# hitchBOT-on-a-board.net
KiCad netlist of a schematic drawn in EAGLE
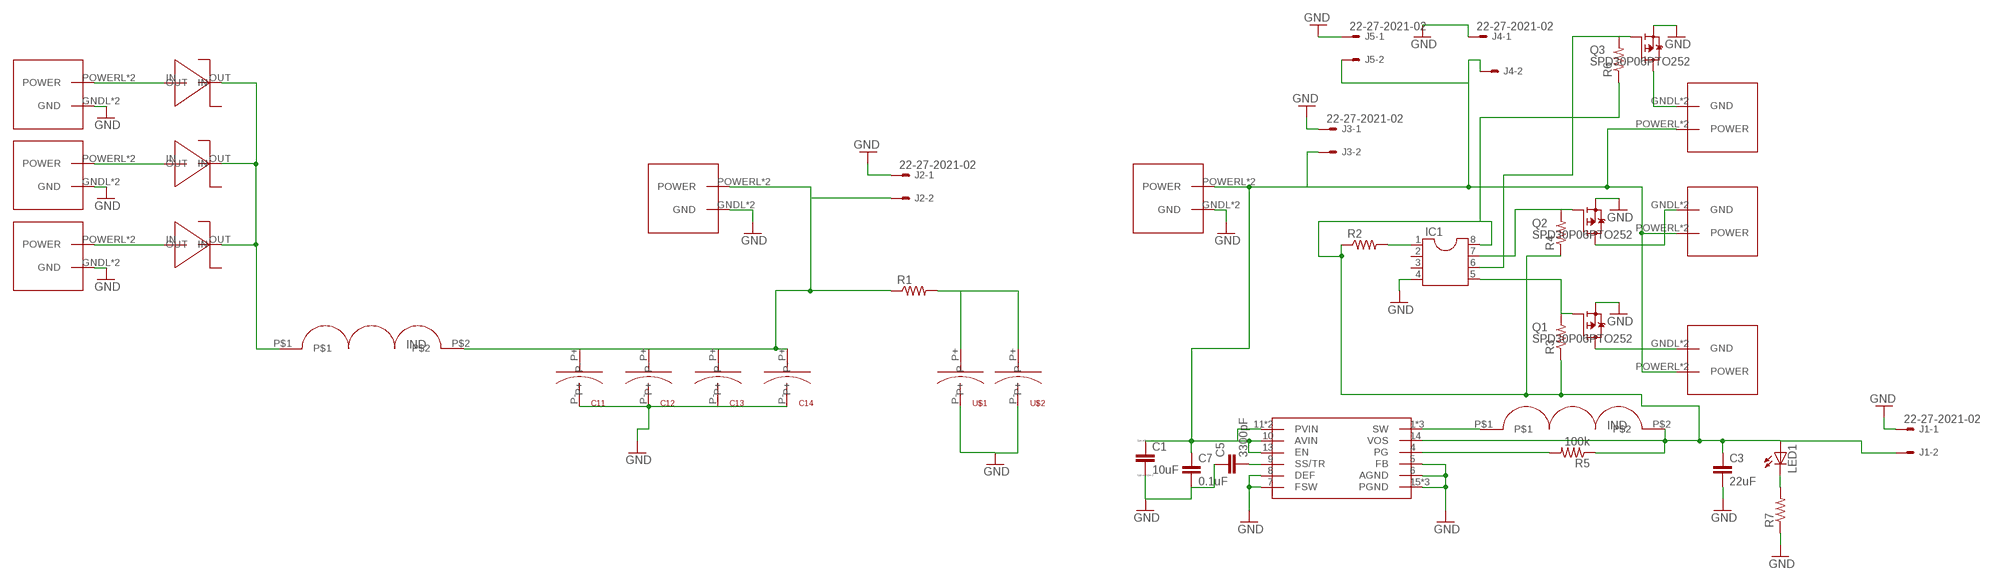
[diagram p0: schematic, sheet 1]

(export (version "E")
  (design (tool "Eeschema 10.0.6"))
  (components
    (comp (ref "C1")
      (value "10uF")
      (footprint "eagle-import:C1210")
      (libsource (lib "eagle-import") (part "CC1210"))
    )
    (comp (ref "C3")
      (value "22uF")
      (footprint "eagle-import:C0805")
      (libsource (lib "eagle-import") (part "C-EUC0805"))
    )
    (comp (ref "C5")
      (value "3300pF")
      (footprint "eagle-import:C0603")
      (libsource (lib "eagle-import") (part "C-EUC0603"))
    )
    (comp (ref "C7")
      (value "0.1uF")
      (footprint "eagle-import:C0603")
      (libsource (lib "eagle-import") (part "C-EUC0603"))
    )
    (comp (ref "C11")
      (value "SMD-CAP-NICHICON-8MM")
      (footprint "eagle-import:SMD-CAP-8MM")
      (libsource (lib "eagle-import") (part "SMD-CAP-NICHICON-8MM"))
    )
    (comp (ref "C12")
      (value "SMD-CAP-NICHICON-8MM")
      (footprint "eagle-import:SMD-CAP-8MM")
      (libsource (lib "eagle-import") (part "SMD-CAP-NICHICON-8MM"))
    )
    (comp (ref "C13")
      (value "SMD-CAP-NICHICON-8MM")
      (footprint "eagle-import:SMD-CAP-8MM")
      (libsource (lib "eagle-import") (part "SMD-CAP-NICHICON-8MM"))
    )
    (comp (ref "C14")
      (value "SMD-CAP-NICHICON-8MM")
      (footprint "eagle-import:SMD-CAP-8MM")
      (libsource (lib "eagle-import") (part "SMD-CAP-NICHICON-8MM"))
    )
    (comp (ref "IC1")
      (value "DIL8S")
      (footprint "eagle-import:SOCKET-08")
      (libsource (lib "eagle-import") (part "DIL8S"))
    )
    (comp (ref "J1")
      (value "22-27-2021-02")
      (footprint "eagle-import:6410-02")
      (libsource (lib "eagle-import") (part "22-?-0227-2021"))
    )
    (comp (ref "J2")
      (value "22-27-2021-02")
      (footprint "eagle-import:6410-02")
      (libsource (lib "eagle-import") (part "22-?-0227-2021"))
    )
    (comp (ref "J3")
      (value "22-27-2021-02")
      (footprint "eagle-import:6410-02")
      (libsource (lib "eagle-import") (part "22-?-0227-2021"))
    )
    (comp (ref "J4")
      (value "22-27-2021-02")
      (footprint "eagle-import:6410-02")
      (libsource (lib "eagle-import") (part "22-?-0227-2021"))
    )
    (comp (ref "J5")
      (value "22-27-2021-02")
      (footprint "eagle-import:6410-02")
      (libsource (lib "eagle-import") (part "22-?-0227-2021"))
    )
    (comp (ref "LED1")
      (value "LEDCHIPLED_1206")
      (footprint "eagle-import:CHIPLED_1206")
      (libsource (lib "eagle-import") (part "LEDCHIPLED_1206"))
    )
    (comp (ref "Q1")
      (value "SPD30P06PTO252")
      (footprint "eagle-import:TO252")
      (libsource (lib "eagle-import") (part "SPD30P06PTO252"))
    )
    (comp (ref "Q2")
      (value "SPD30P06PTO252")
      (footprint "eagle-import:TO252")
      (libsource (lib "eagle-import") (part "SPD30P06PTO252"))
    )
    (comp (ref "Q3")
      (value "SPD30P06PTO252")
      (footprint "eagle-import:TO252")
      (libsource (lib "eagle-import") (part "SPD30P06PTO252"))
    )
    (comp (ref "R1")
      (value "R-US_R1206")
      (footprint "eagle-import:R1206")
      (libsource (lib "eagle-import") (part "resistor_R-US_R1206"))
    )
    (comp (ref "R2")
      (value "R-US_R1206")
      (footprint "eagle-import:R1206")
      (libsource (lib "eagle-import") (part "resistor_R-US_R1206"))
    )
    (comp (ref "R3")
      (value "R-US_R1206")
      (footprint "eagle-import:R1206")
      (libsource (lib "eagle-import") (part "resistor_R-US_R1206"))
    )
    (comp (ref "R4")
      (value "R-US_R1206")
      (footprint "eagle-import:R1206")
      (libsource (lib "eagle-import") (part "resistor_R-US_R1206"))
    )
    (comp (ref "R5")
      (value "100k")
      (footprint "eagle-import:R1206")
      (libsource (lib "eagle-import") (part "resistor_R-US_R1206"))
    )
    (comp (ref "R6")
      (value "R-US_R1206")
      (footprint "eagle-import:R1206")
      (libsource (lib "eagle-import") (part "resistor_R-US_R1206"))
    )
    (comp (ref "R7")
      (value "R-US_R1206")
      (footprint "eagle-import:R1206")
      (libsource (lib "eagle-import") (part "R-US_R1206"))
    )
    (comp (ref "U$1")
      (value "SMD-CAP-PANASONIC-E-FT-10MM")
      (footprint "eagle-import:SMD-CAP-10MM")
      (libsource (lib "eagle-import") (part "SMD-CAP-PANASONIC-E-FT-10MM"))
    )
    (comp (ref "U$2")
      (value "SMD-CAP-PANASONIC-E-FT-10MM")
      (footprint "eagle-import:SMD-CAP-10MM")
      (libsource (lib "eagle-import") (part "SMD-CAP-PANASONIC-E-FT-10MM"))
    )
    (comp (ref "U$3")
      (value "INDUCTOR-M8365")
      (footprint "eagle-import:INDUCTOR-M8365")
      (libsource (lib "eagle-import") (part "INDUCTOR-M8365"))
    )
    (comp (ref "U$4")
      (value "2X2-MOLEX")
      (footprint "eagle-import:2X2MOLEX")
      (libsource (lib "eagle-import") (part "2X2-MOLEX"))
    )
    (comp (ref "U$5")
      (value "2X2-MOLEX")
      (footprint "eagle-import:2X2MOLEX")
      (libsource (lib "eagle-import") (part "2X2-MOLEX"))
    )
    (comp (ref "U$6")
      (value "2X2-MOLEX")
      (footprint "eagle-import:2X2MOLEX")
      (libsource (lib "eagle-import") (part "2X2-MOLEX"))
    )
    (comp (ref "U$7")
      (value "DO-214AB")
      (footprint "eagle-import:DO-214AB")
      (libsource (lib "eagle-import") (part "DO-214AB"))
    )
    (comp (ref "U$8")
      (value "DO-214AB")
      (footprint "eagle-import:DO-214AB")
      (libsource (lib "eagle-import") (part "DO-214AB"))
    )
    (comp (ref "U$9")
      (value "DO-214AB")
      (footprint "eagle-import:DO-214AB")
      (libsource (lib "eagle-import") (part "DO-214AB"))
    )
    (comp (ref "U$10")
      (value "2X2-MOLEX")
      (footprint "eagle-import:2X2MOLEX")
      (libsource (lib "eagle-import") (part "2X2-MOLEX"))
    )
    (comp (ref "U$11")
      (value "2X2-MOLEX")
      (footprint "eagle-import:2X2MOLEX")
      (libsource (lib "eagle-import") (part "2X2-MOLEX"))
    )
    (comp (ref "U$12")
      (value "2X2-MOLEX")
      (footprint "eagle-import:2X2MOLEX")
      (libsource (lib "eagle-import") (part "2X2-MOLEX"))
    )
    (comp (ref "U$13")
      (value "2X2-MOLEX")
      (footprint "eagle-import:2X2MOLEX")
      (libsource (lib "eagle-import") (part "2X2-MOLEX"))
    )
    (comp (ref "U$14")
      (value "TPS62133")
      (footprint "eagle-import:QFN16")
      (libsource (lib "eagle-import") (part "TPS62133"))
    )
    (comp (ref "U$15")
      (value "DR73-2R2-R")
      (footprint "eagle-import:DR73-2R2-R")
      (libsource (lib "eagle-import") (part "DR73-2R2-R"))
    )
    (comp (ref "U$17")
      (value "2X2-MOLEX")
      (footprint "eagle-import:2X2MOLEX")
      (libsource (lib "eagle-import") (part "2X2-MOLEX"))
    )
  )
  (nets
    (net (code "1") (name "GND") (class "Default")
      (node (ref "C1") (pin "2") (pinfunction "2_2") (pintype "passive"))
      (node (ref "C11") (pin "P-") (pinfunction "P-_P-") (pintype "bidirectional"))
      (node (ref "C12") (pin "P-") (pinfunction "P-_P-") (pintype "bidirectional"))
      (node (ref "C13") (pin "P-") (pinfunction "P-_P-") (pintype "bidirectional"))
      (node (ref "C14") (pin "P-") (pinfunction "P-_P-") (pintype "bidirectional"))
      (node (ref "C3") (pin "2") (pinfunction "2_2") (pintype "passive"))
      (node (ref "C5") (pin "1") (pinfunction "1_1") (pintype "passive"))
      (node (ref "C7") (pin "2") (pinfunction "2_2") (pintype "passive"))
      (node (ref "IC1") (pin "4") (pinfunction "4_4") (pintype "passive"))
      (node (ref "J1") (pin "1") (pinfunction "S_1") (pintype "passive"))
      (node (ref "J2") (pin "1") (pinfunction "S_1") (pintype "passive"))
      (node (ref "J3") (pin "1") (pinfunction "S_1") (pintype "passive"))
      (node (ref "J4") (pin "1") (pinfunction "S_1") (pintype "passive"))
      (node (ref "J5") (pin "1") (pinfunction "S_1") (pintype "passive"))
      (node (ref "Q1") (pin "2") (pinfunction "S_2") (pintype "passive"))
      (node (ref "Q2") (pin "2") (pinfunction "S_2") (pintype "passive"))
      (node (ref "Q3") (pin "2") (pinfunction "S_2") (pintype "passive"))
      (node (ref "R7") (pin "1") (pinfunction "1_1") (pintype "passive"))
      (node (ref "U$1") (pin "P-") (pinfunction "P-_P-") (pintype "bidirectional"))
      (node (ref "U$10") (pin "GNDL") (pinfunction "GND_GNDL") (pintype "bidirectional"))
      (node (ref "U$10") (pin "GNDR") (pinfunction "GND_GNDR") (pintype "bidirectional"))
      (node (ref "U$11") (pin "GNDL") (pinfunction "GND_GNDL") (pintype "bidirectional"))
      (node (ref "U$11") (pin "GNDR") (pinfunction "GND_GNDR") (pintype "bidirectional"))
      (node (ref "U$14") (pin "15") (pinfunction "PGND_15") (pintype "bidirectional"))
      (node (ref "U$14") (pin "16") (pinfunction "PGND_16") (pintype "bidirectional"))
      (node (ref "U$14") (pin "5") (pinfunction "FB_5") (pintype "bidirectional"))
      (node (ref "U$14") (pin "6") (pinfunction "AGND_6") (pintype "bidirectional"))
      (node (ref "U$14") (pin "7") (pinfunction "FSW_7") (pintype "bidirectional"))
      (node (ref "U$14") (pin "8") (pinfunction "DEF_8") (pintype "bidirectional"))
      (node (ref "U$14") (pin "P$1") (pinfunction "PGND_P$1") (pintype "bidirectional"))
      (node (ref "U$2") (pin "P-") (pinfunction "P-_P-") (pintype "bidirectional"))
      (node (ref "U$4") (pin "GNDL") (pinfunction "GND_GNDL") (pintype "bidirectional"))
      (node (ref "U$4") (pin "GNDR") (pinfunction "GND_GNDR") (pintype "bidirectional"))
      (node (ref "U$5") (pin "GNDL") (pinfunction "GND_GNDL") (pintype "bidirectional"))
      (node (ref "U$5") (pin "GNDR") (pinfunction "GND_GNDR") (pintype "bidirectional"))
      (node (ref "U$6") (pin "GNDL") (pinfunction "GND_GNDL") (pintype "bidirectional"))
      (node (ref "U$6") (pin "GNDR") (pinfunction "GND_GNDR") (pintype "bidirectional"))
    )
    (net (code "2") (name "Net-(IC1-Pad1)") (class "Default")
      (node (ref "IC1") (pin "1") (pinfunction "1_1") (pintype "passive"))
      (node (ref "R2") (pin "2") (pinfunction "2_2") (pintype "passive"))
    )
    (net (code "3") (name "Net-(J1B-S)") (class "Default")
      (node (ref "C3") (pin "1") (pinfunction "1_1") (pintype "passive"))
      (node (ref "IC1") (pin "8") (pinfunction "8_8") (pintype "passive"))
      (node (ref "J1") (pin "2") (pinfunction "S_2") (pintype "passive"))
      (node (ref "LED1") (pin "A") (pinfunction "A_A") (pintype "passive"))
      (node (ref "R2") (pin "1") (pinfunction "1_1") (pintype "passive"))
      (node (ref "R3") (pin "1") (pinfunction "1_1") (pintype "passive"))
      (node (ref "R4") (pin "1") (pinfunction "1_1") (pintype "passive"))
      (node (ref "R5") (pin "1") (pinfunction "1_1") (pintype "passive"))
      (node (ref "R6") (pin "1") (pinfunction "1_1") (pintype "passive"))
      (node (ref "U$14") (pin "14") (pinfunction "VOS_14") (pintype "bidirectional"))
      (node (ref "U$15") (pin "P$2") (pinfunction "P$2_P$2") (pintype "bidirectional"))
    )
    (net (code "4") (name "Net-(J2B-S)") (class "Default")
      (node (ref "C11") (pin "P+") (pinfunction "P+_P+") (pintype "bidirectional"))
      (node (ref "C12") (pin "P+") (pinfunction "P+_P+") (pintype "bidirectional"))
      (node (ref "C13") (pin "P+") (pinfunction "P+_P+") (pintype "bidirectional"))
      (node (ref "C14") (pin "P+") (pinfunction "P+_P+") (pintype "bidirectional"))
      (node (ref "J2") (pin "2") (pinfunction "S_2") (pintype "passive"))
      (node (ref "R1") (pin "1") (pinfunction "1_1") (pintype "passive"))
      (node (ref "U$10") (pin "POWERL") (pinfunction "POWER_POWERL") (pintype "bidirectional"))
      (node (ref "U$10") (pin "POWERR") (pinfunction "POWER_POWERR") (pintype "bidirectional"))
      (node (ref "U$3") (pin "P$2") (pinfunction "P$2_P$2") (pintype "bidirectional"))
    )
    (net (code "5") (name "Net-(J3B-S)") (class "Default")
      (node (ref "C1") (pin "1") (pinfunction "1_1") (pintype "passive"))
      (node (ref "C7") (pin "1") (pinfunction "1_1") (pintype "passive"))
      (node (ref "J3") (pin "2") (pinfunction "S_2") (pintype "passive"))
      (node (ref "J4") (pin "2") (pinfunction "S_2") (pintype "passive"))
      (node (ref "J5") (pin "2") (pinfunction "S_2") (pintype "passive"))
      (node (ref "U$11") (pin "POWERL") (pinfunction "POWER_POWERL") (pintype "bidirectional"))
      (node (ref "U$11") (pin "POWERR") (pinfunction "POWER_POWERR") (pintype "bidirectional"))
      (node (ref "U$12") (pin "POWERL") (pinfunction "POWER_POWERL") (pintype "bidirectional"))
      (node (ref "U$12") (pin "POWERR") (pinfunction "POWER_POWERR") (pintype "bidirectional"))
      (node (ref "U$13") (pin "POWERL") (pinfunction "POWER_POWERL") (pintype "bidirectional"))
      (node (ref "U$13") (pin "POWERR") (pinfunction "POWER_POWERR") (pintype "bidirectional"))
      (node (ref "U$14") (pin "10") (pinfunction "AVIN_10") (pintype "bidirectional"))
      (node (ref "U$14") (pin "11") (pinfunction "PVIN_11") (pintype "bidirectional"))
      (node (ref "U$14") (pin "12") (pinfunction "PVIN_12") (pintype "bidirectional"))
      (node (ref "U$14") (pin "13") (pinfunction "EN_13") (pintype "bidirectional"))
      (node (ref "U$17") (pin "POWERL") (pinfunction "POWER_POWERL") (pintype "bidirectional"))
      (node (ref "U$17") (pin "POWERR") (pinfunction "POWER_POWERR") (pintype "bidirectional"))
    )
    (net (code "6") (name "Net-(LED1-PadC)") (class "Default")
      (node (ref "LED1") (pin "C") (pinfunction "C_C") (pintype "passive"))
      (node (ref "R7") (pin "2") (pinfunction "2_2") (pintype "passive"))
    )
    (net (code "7") (name "Net-(Q1-D)") (class "Default")
      (node (ref "Q1") (pin "3") (pinfunction "D_3") (pintype "passive"))
      (node (ref "U$13") (pin "GNDL") (pinfunction "GND_GNDL") (pintype "bidirectional"))
      (node (ref "U$13") (pin "GNDR") (pinfunction "GND_GNDR") (pintype "bidirectional"))
    )
    (net (code "8") (name "Net-(Q1-G)") (class "Default")
      (node (ref "IC1") (pin "5") (pinfunction "5_5") (pintype "passive"))
      (node (ref "Q1") (pin "1") (pinfunction "G_1") (pintype "passive"))
      (node (ref "R3") (pin "2") (pinfunction "2_2") (pintype "passive"))
    )
    (net (code "9") (name "Net-(Q2-D)") (class "Default")
      (node (ref "Q2") (pin "3") (pinfunction "D_3") (pintype "passive"))
      (node (ref "U$12") (pin "GNDL") (pinfunction "GND_GNDL") (pintype "bidirectional"))
      (node (ref "U$12") (pin "GNDR") (pinfunction "GND_GNDR") (pintype "bidirectional"))
    )
    (net (code "10") (name "Net-(Q2-G)") (class "Default")
      (node (ref "IC1") (pin "7") (pinfunction "7_7") (pintype "passive"))
      (node (ref "Q2") (pin "1") (pinfunction "G_1") (pintype "passive"))
      (node (ref "R4") (pin "2") (pinfunction "2_2") (pintype "passive"))
    )
    (net (code "11") (name "Net-(Q3-D)") (class "Default")
      (node (ref "Q3") (pin "3") (pinfunction "D_3") (pintype "passive"))
      (node (ref "U$17") (pin "GNDL") (pinfunction "GND_GNDL") (pintype "bidirectional"))
      (node (ref "U$17") (pin "GNDR") (pinfunction "GND_GNDR") (pintype "bidirectional"))
    )
    (net (code "12") (name "Net-(Q3-G)") (class "Default")
      (node (ref "IC1") (pin "6") (pinfunction "6_6") (pintype "passive"))
      (node (ref "Q3") (pin "1") (pinfunction "G_1") (pintype "passive"))
      (node (ref "R6") (pin "2") (pinfunction "2_2") (pintype "passive"))
    )
    (net (code "13") (name "Net-(R1-Pad2)") (class "Default")
      (node (ref "R1") (pin "2") (pinfunction "2_2") (pintype "passive"))
      (node (ref "U$1") (pin "P+") (pinfunction "P+_P+") (pintype "bidirectional"))
      (node (ref "U$2") (pin "P+") (pinfunction "P+_P+") (pintype "bidirectional"))
    )
    (net (code "14") (name "Net-(U$3-PadP$1)") (class "Default")
      (node (ref "U$3") (pin "P$1") (pinfunction "P$1_P$1") (pintype "bidirectional"))
      (node (ref "U$7") (pin "OUT") (pinfunction "OUT_OUT") (pintype "bidirectional"))
      (node (ref "U$8") (pin "OUT") (pinfunction "OUT_OUT") (pintype "bidirectional"))
      (node (ref "U$9") (pin "OUT") (pinfunction "OUT_OUT") (pintype "bidirectional"))
    )
    (net (code "15") (name "Net-(U$4-POWER-PadPOWERL)") (class "Default")
      (node (ref "U$4") (pin "POWERL") (pinfunction "POWER_POWERL") (pintype "bidirectional"))
      (node (ref "U$4") (pin "POWERR") (pinfunction "POWER_POWERR") (pintype "bidirectional"))
      (node (ref "U$9") (pin "IN") (pinfunction "IN_IN") (pintype "bidirectional"))
    )
    (net (code "16") (name "Net-(U$5-POWER-PadPOWERL)") (class "Default")
      (node (ref "U$5") (pin "POWERL") (pinfunction "POWER_POWERL") (pintype "bidirectional"))
      (node (ref "U$5") (pin "POWERR") (pinfunction "POWER_POWERR") (pintype "bidirectional"))
      (node (ref "U$7") (pin "IN") (pinfunction "IN_IN") (pintype "bidirectional"))
    )
    (net (code "17") (name "Net-(U$6-POWER-PadPOWERL)") (class "Default")
      (node (ref "U$6") (pin "POWERL") (pinfunction "POWER_POWERL") (pintype "bidirectional"))
      (node (ref "U$6") (pin "POWERR") (pinfunction "POWER_POWERR") (pintype "bidirectional"))
      (node (ref "U$8") (pin "IN") (pinfunction "IN_IN") (pintype "bidirectional"))
    )
    (net (code "18") (name "Net-(U$14-PG)") (class "Default")
      (node (ref "R5") (pin "2") (pinfunction "2_2") (pintype "passive"))
      (node (ref "U$14") (pin "4") (pinfunction "PG_4") (pintype "bidirectional"))
    )
    (net (code "19") (name "Net-(U$14-SS{slash}TR)") (class "Default")
      (node (ref "C5") (pin "2") (pinfunction "2_2") (pintype "passive"))
      (node (ref "U$14") (pin "9") (pinfunction "SS/TR_9") (pintype "bidirectional"))
    )
    (net (code "20") (name "Net-(U$14-SW-Pad1)") (class "Default")
      (node (ref "U$14") (pin "1") (pinfunction "SW_1") (pintype "bidirectional"))
      (node (ref "U$14") (pin "2") (pinfunction "SW_2") (pintype "bidirectional"))
      (node (ref "U$14") (pin "3") (pinfunction "SW_3") (pintype "bidirectional"))
      (node (ref "U$15") (pin "P$1") (pinfunction "P$1_P$1") (pintype "bidirectional"))
    )
    (net (code "21") (name "unconnected-(IC1-Pad2)") (class "Default")
      (node (ref "IC1") (pin "2") (pinfunction "2_2") (pintype "passive"))
    )
    (net (code "22") (name "unconnected-(IC1-Pad3)") (class "Default")
      (node (ref "IC1") (pin "3") (pinfunction "3_3") (pintype "passive"))
    )
  )
)
